# Power_Board_DCDC3V3.net
KiCad netlist of a schematic drawn in Altium Designer
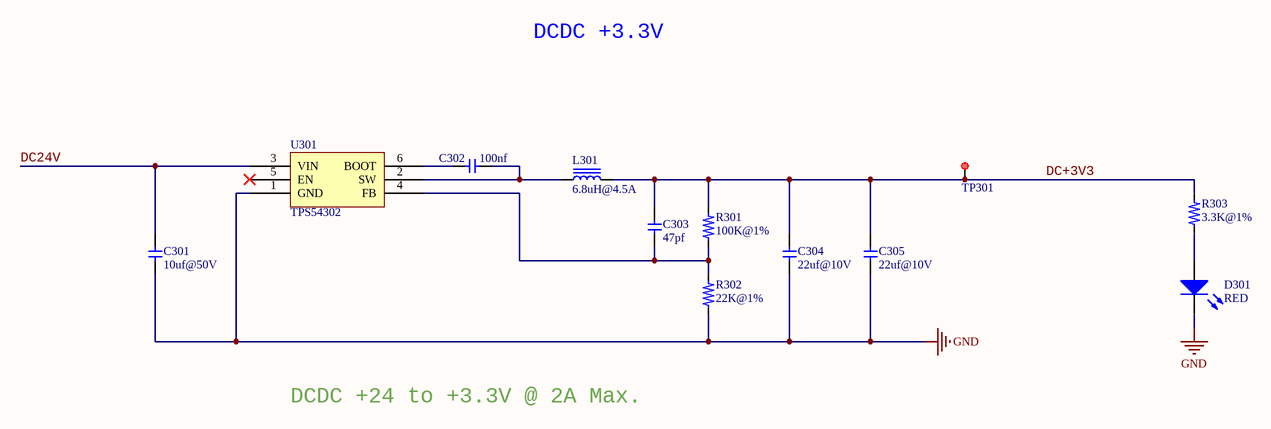
[diagram p0: Power Board.DCDC3V3.SchDoc]

(export (version "E")
  (design (tool "Eeschema 10.0.6"))
  (components
    (comp (ref "C301")
      (value "10uf@50V")
      (footprint "C1206")
      (fields (field (name "Comment") "Cap"))
      (libsource (lib "carrot_lib") (part "Cap"))
    )
    (comp (ref "C302")
      (value "100nf")
      (footprint "C0603")
      (fields (field (name "Comment") "Cap"))
      (libsource (lib "carrot_lib") (part "Cap"))
    )
    (comp (ref "C303")
      (value "47pf")
      (footprint "C0603")
      (fields (field (name "Comment") "Cap"))
      (libsource (lib "carrot_lib") (part "Cap"))
    )
    (comp (ref "C304")
      (value "22uf@10V")
      (footprint "C1206")
      (fields (field (name "Comment") "Cap"))
      (libsource (lib "carrot_lib") (part "Cap"))
    )
    (comp (ref "C305")
      (value "22uf@10V")
      (footprint "C1206")
      (fields (field (name "Comment") "Cap"))
      (libsource (lib "carrot_lib") (part "Cap"))
    )
    (comp (ref "D301")
      (value "RED")
      (footprint "LED0603")
      (fields (field (name "Comment") "LED"))
      (libsource (lib "carrot_lib") (part "LED"))
    )
    (comp (ref "L301")
      (value "6.8uH@4.5A")
      (footprint "L06063")
      (description "Magnetic-Core Inductor")
      (fields (field (name "Comment") "Inductor Iron"))
      (libsource (lib "carrot_lib") (part "Inductor Iron"))
    )
    (comp (ref "R301")
      (value "100K@1%")
      (footprint "R0603")
      (description "电阻")
      (fields (field (name "Comment") "Res"))
      (libsource (lib "carrot_lib") (part "Res"))
    )
    (comp (ref "R302")
      (value "22K@1%")
      (footprint "R0603")
      (description "电阻")
      (fields (field (name "Comment") "Res"))
      (libsource (lib "carrot_lib") (part "Res"))
    )
    (comp (ref "R303")
      (value "3.3K@1%")
      (footprint "R0603")
      (description "电阻")
      (fields (field (name "Comment") "Res"))
      (libsource (lib "carrot_lib") (part "Res"))
    )
    (comp (ref "TP301")
      (value "TestPoint")
      (footprint "TestPoint-THM1.0-L")
      (description "测试点")
      (libsource (lib "carrot_lib") (part "TestPoint"))
    )
    (comp (ref "U301")
      (value "TPS54302")
      (footprint "TPS54302-SOT23-6")
      (description "TPS54302 4.5-V to 28-V Input, 3-A Output, EMI-Friendly Synchronous Step-Down Converter")
      (libsource (lib "carrot_lib") (part "TPS54302"))
    )
  )
  (nets
    (net (code "1") (name "/DC+3V3") (class "Default")
      (node (ref "C303") (pin "1") (pinfunction "1_1") (pintype "passive"))
      (node (ref "C304") (pin "2") (pinfunction "2_2") (pintype "passive"))
      (node (ref "C305") (pin "2") (pinfunction "2_2") (pintype "passive"))
      (node (ref "L301") (pin "2") (pinfunction "2_2") (pintype "passive"))
      (node (ref "R301") (pin "2") (pinfunction "2_2") (pintype "passive"))
      (node (ref "R303") (pin "2") (pinfunction "2_2") (pintype "passive"))
      (node (ref "TP301") (pin "1") (pinfunction "1_1") (pintype "passive"))
    )
    (net (code "2") (name "/DC24V") (class "Default")
      (node (ref "C301") (pin "2") (pinfunction "2_2") (pintype "passive"))
      (node (ref "U301") (pin "3") (pinfunction "VIN_3") (pintype "passive"))
    )
    (net (code "3") (name "GND") (class "Default")
      (node (ref "C301") (pin "1") (pinfunction "1_1") (pintype "passive"))
      (node (ref "C304") (pin "1") (pinfunction "1_1") (pintype "passive"))
      (node (ref "C305") (pin "1") (pinfunction "1_1") (pintype "passive"))
      (node (ref "D301") (pin "2") (pinfunction "K_2") (pintype "passive"))
      (node (ref "R302") (pin "1") (pinfunction "1_1") (pintype "passive"))
      (node (ref "U301") (pin "1") (pinfunction "GND_1") (pintype "passive"))
    )
    (net (code "4") (name "Net-(D301-A)") (class "Default")
      (node (ref "D301") (pin "1") (pinfunction "A_1") (pintype "passive"))
      (node (ref "R303") (pin "1") (pinfunction "1_1") (pintype "passive"))
    )
    (net (code "5") (name "Net-(U301-BOOT)") (class "Default")
      (node (ref "C302") (pin "2") (pinfunction "2_2") (pintype "passive"))
      (node (ref "U301") (pin "6") (pinfunction "BOOT_6") (pintype "passive"))
    )
    (net (code "6") (name "Net-(U301-FB)") (class "Default")
      (node (ref "C303") (pin "2") (pinfunction "2_2") (pintype "passive"))
      (node (ref "R301") (pin "1") (pinfunction "1_1") (pintype "passive"))
      (node (ref "R302") (pin "2") (pinfunction "2_2") (pintype "passive"))
      (node (ref "U301") (pin "4") (pinfunction "FB_4") (pintype "passive"))
    )
    (net (code "7") (name "Net-(U301-SW)") (class "Default")
      (node (ref "C302") (pin "1") (pinfunction "1_1") (pintype "passive"))
      (node (ref "L301") (pin "1") (pinfunction "1_1") (pintype "passive"))
      (node (ref "U301") (pin "2") (pinfunction "SW_2") (pintype "passive"))
    )
    (net (code "8") (name "unconnected-(U301-EN-Pad5)") (class "Default")
      (node (ref "U301") (pin "5") (pinfunction "EN_5") (pintype "passive+no_connect"))
    )
  )
)
